# VCAMixer.net
KiCad netlist of a schematic drawn in EAGLE
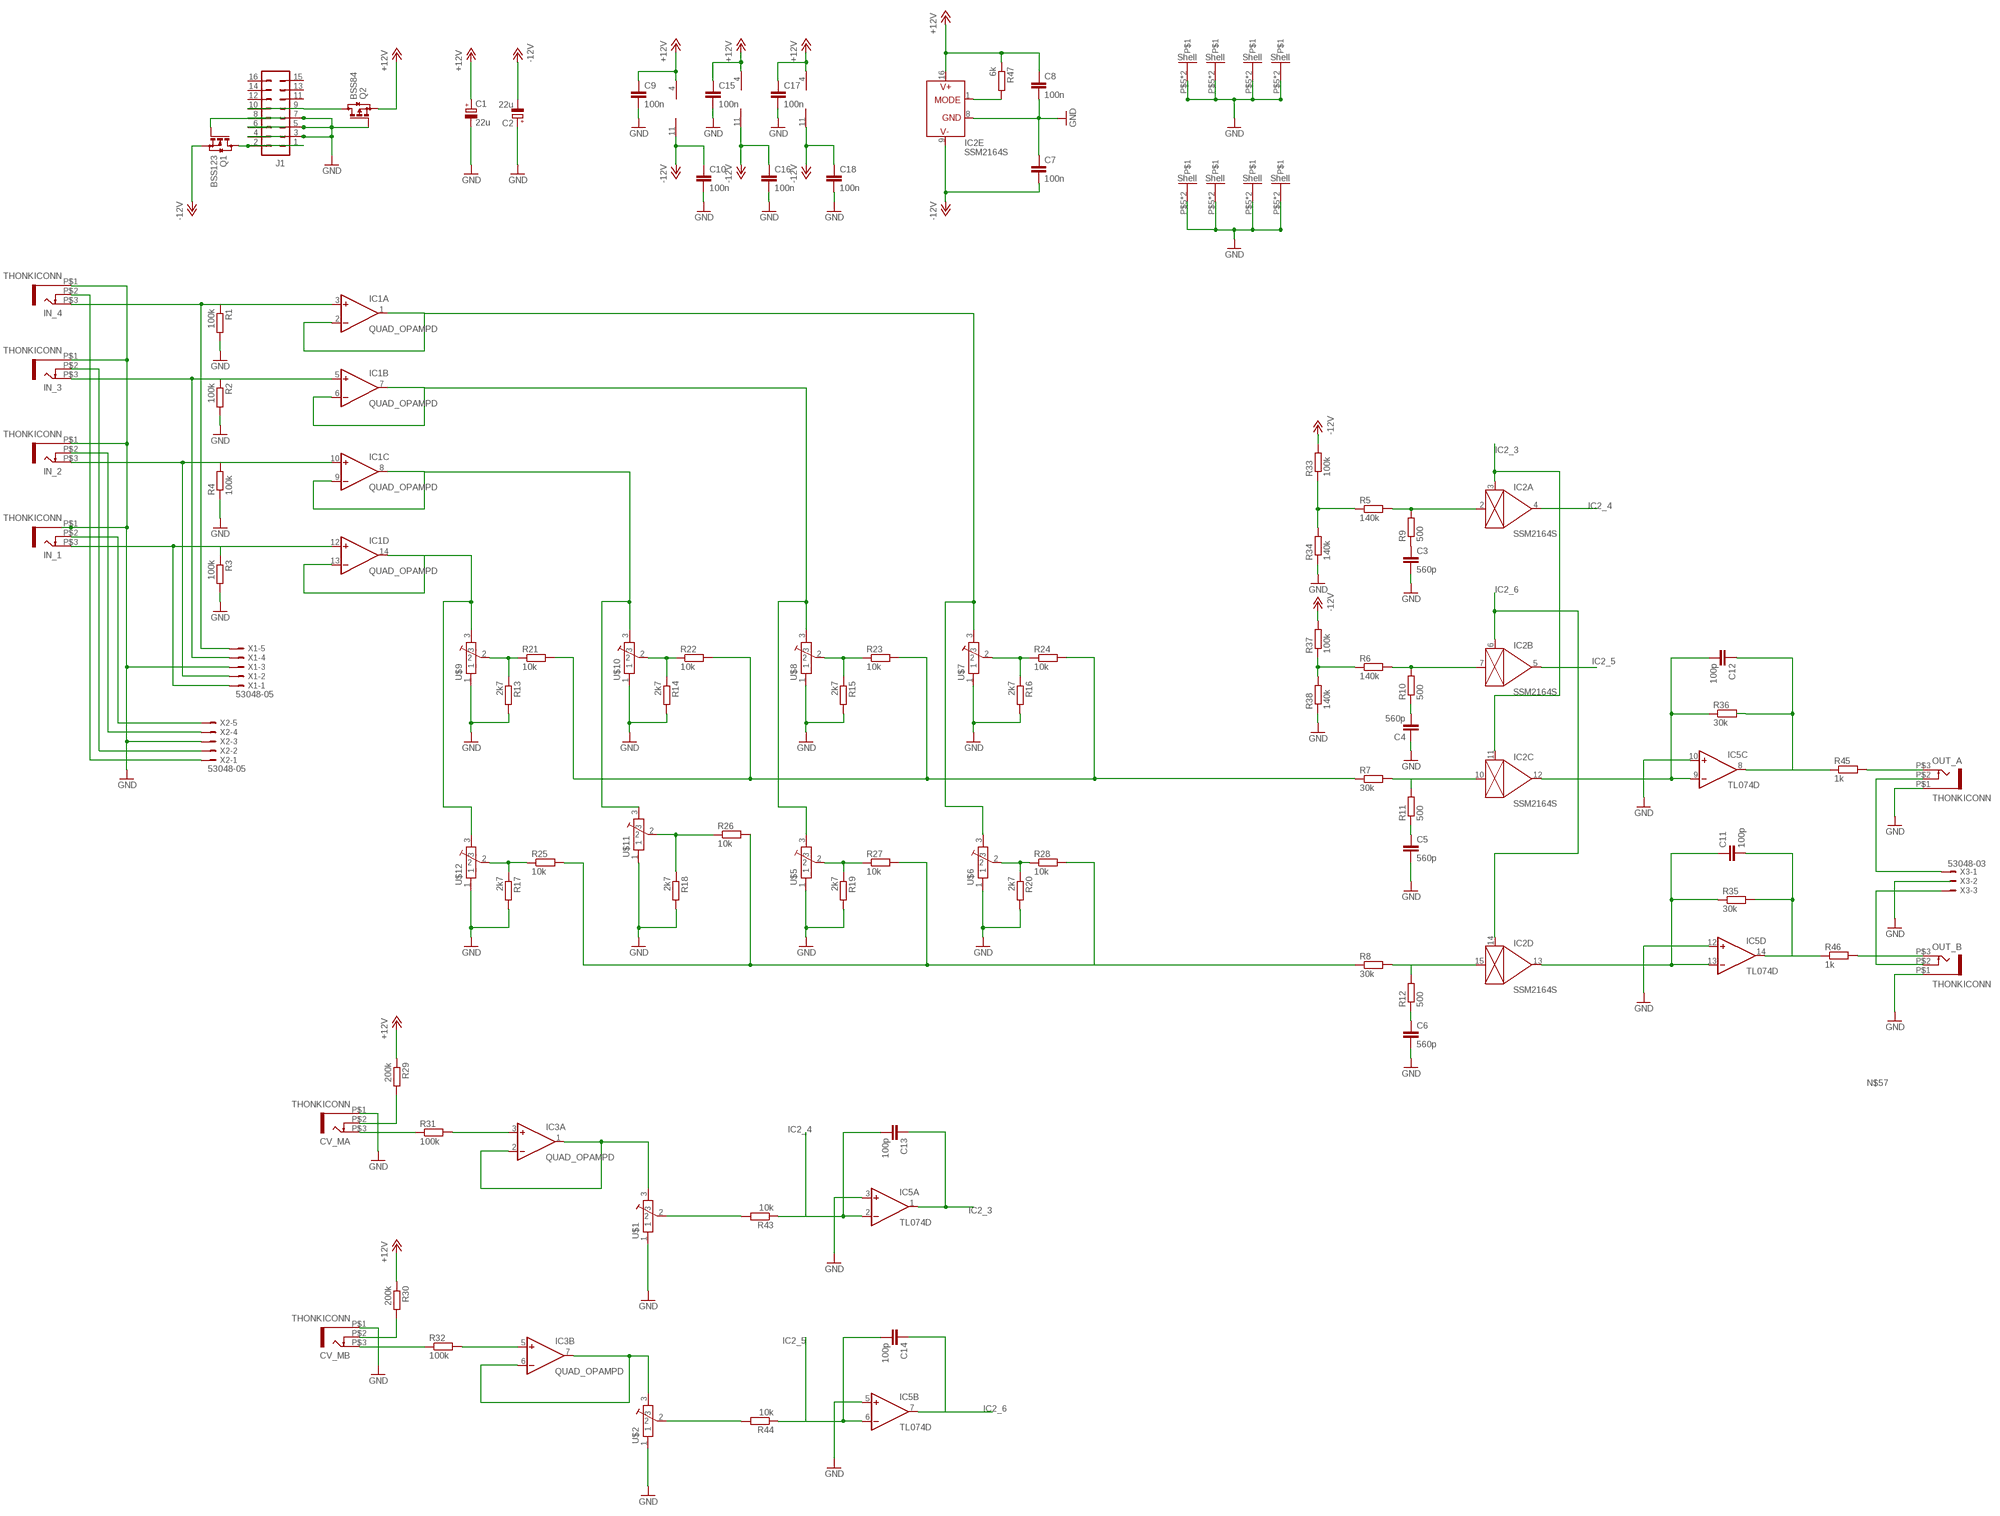
[diagram p0: schematic, sheet 1]

(export (version "E")
  (design (tool "Eeschema 10.0.6"))
  (components
    (comp (ref "C1")
      (value "22u")
      (footprint "eagle-import:153CLV-0505")
      (libsource (lib "eagle-import") (part "CPOL-EU153CLV-0505"))
    )
    (comp (ref "C2")
      (value "22u")
      (footprint "eagle-import:153CLV-0505")
      (libsource (lib "eagle-import") (part "CPOL-EU153CLV-0505"))
    )
    (comp (ref "C3")
      (value "560p")
      (footprint "eagle-import:C0603K")
      (libsource (lib "eagle-import") (part "C-EUC0603K"))
    )
    (comp (ref "C4")
      (value "560p")
      (footprint "eagle-import:C0603K")
      (libsource (lib "eagle-import") (part "C-EUC0603K"))
    )
    (comp (ref "C5")
      (value "560p")
      (footprint "eagle-import:C0603K")
      (libsource (lib "eagle-import") (part "C-EUC0603K"))
    )
    (comp (ref "C6")
      (value "560p")
      (footprint "eagle-import:C0603K")
      (libsource (lib "eagle-import") (part "C-EUC0603K"))
    )
    (comp (ref "C7")
      (value "100n")
      (footprint "eagle-import:C0603K")
      (libsource (lib "eagle-import") (part "C-EUC0603K"))
    )
    (comp (ref "C8")
      (value "100n")
      (footprint "eagle-import:C0603K")
      (libsource (lib "eagle-import") (part "C-EUC0603K"))
    )
    (comp (ref "C9")
      (value "100n")
      (footprint "eagle-import:C0603K")
      (libsource (lib "eagle-import") (part "C-EUC0603K"))
    )
    (comp (ref "C10")
      (value "100n")
      (footprint "eagle-import:C0603K")
      (libsource (lib "eagle-import") (part "C-EUC0603K"))
    )
    (comp (ref "C11")
      (value "100p")
      (footprint "eagle-import:C0603K")
      (libsource (lib "eagle-import") (part "C-EUC0603K"))
    )
    (comp (ref "C12")
      (value "100p")
      (footprint "eagle-import:C0603K")
      (libsource (lib "eagle-import") (part "C-EUC0603K"))
    )
    (comp (ref "C13")
      (value "100p")
      (footprint "eagle-import:C0603K")
      (libsource (lib "eagle-import") (part "C-EUC0603K"))
    )
    (comp (ref "C14")
      (value "100p")
      (footprint "eagle-import:C0603K")
      (libsource (lib "eagle-import") (part "C-EUC0603K"))
    )
    (comp (ref "C15")
      (value "100n")
      (footprint "eagle-import:C0603K")
      (libsource (lib "eagle-import") (part "C-EUC0603K"))
    )
    (comp (ref "C16")
      (value "100n")
      (footprint "eagle-import:C0603K")
      (libsource (lib "eagle-import") (part "C-EUC0603K"))
    )
    (comp (ref "C17")
      (value "100n")
      (footprint "eagle-import:C0603K")
      (libsource (lib "eagle-import") (part "C-EUC0603K"))
    )
    (comp (ref "C18")
      (value "100n")
      (footprint "eagle-import:C0603K")
      (libsource (lib "eagle-import") (part "C-EUC0603K"))
    )
    (comp (ref "CV_MA")
      (value "THONKICONN")
      (footprint "eagle-import:THONKICONN")
      (libsource (lib "eagle-import") (part "THONKICONN"))
    )
    (comp (ref "CV_MB")
      (value "THONKICONN")
      (footprint "eagle-import:THONKICONN")
      (libsource (lib "eagle-import") (part "THONKICONN"))
    )
    (comp (ref "IC1")
      (value "QUAD_OPAMPD")
      (footprint "eagle-import:SO14")
      (libsource (lib "eagle-import") (part "QUAD_OPAMPD"))
    )
    (comp (ref "IC2")
      (value "SSM2164S")
      (footprint "eagle-import:SOIC16N")
      (libsource (lib "eagle-import") (part "SSM2164S"))
    )
    (comp (ref "IC3")
      (value "QUAD_OPAMPD")
      (footprint "eagle-import:SO14")
      (libsource (lib "eagle-import") (part "QUAD_OPAMPD"))
    )
    (comp (ref "IC5")
      (value "TL074D")
      (footprint "eagle-import:SO14")
      (libsource (lib "eagle-import") (part "TL074D"))
    )
    (comp (ref "IN_1")
      (value "THONKICONN")
      (footprint "eagle-import:THONKICONN")
      (libsource (lib "eagle-import") (part "THONKICONN"))
    )
    (comp (ref "IN_2")
      (value "THONKICONN")
      (footprint "eagle-import:THONKICONN")
      (libsource (lib "eagle-import") (part "THONKICONN"))
    )
    (comp (ref "IN_3")
      (value "THONKICONN")
      (footprint "eagle-import:THONKICONN")
      (libsource (lib "eagle-import") (part "THONKICONN"))
    )
    (comp (ref "IN_4")
      (value "THONKICONN")
      (footprint "eagle-import:THONKICONN")
      (libsource (lib "eagle-import") (part "THONKICONN"))
    )
    (comp (ref "J1")
      (value "M08X2")
      (footprint "eagle-import:2X8")
      (libsource (lib "eagle-import") (part "M08X2"))
    )
    (comp (ref "OUT_A")
      (value "THONKICONN")
      (footprint "eagle-import:THONKICONN")
      (libsource (lib "eagle-import") (part "THONKICONN"))
    )
    (comp (ref "OUT_B")
      (value "THONKICONN")
      (footprint "eagle-import:THONKICONN")
      (libsource (lib "eagle-import") (part "THONKICONN"))
    )
    (comp (ref "Q1")
      (value "BSS123")
      (footprint "eagle-import:SOT23")
      (libsource (lib "eagle-import") (part "BSS123"))
    )
    (comp (ref "Q2")
      (value "BSS84")
      (footprint "eagle-import:SOT23")
      (libsource (lib "eagle-import") (part "BSS84"))
    )
    (comp (ref "R1")
      (value "100k")
      (footprint "eagle-import:0603")
      (libsource (lib "eagle-import") (part "R-EU_0603"))
    )
    (comp (ref "R2")
      (value "100k")
      (footprint "eagle-import:0603")
      (libsource (lib "eagle-import") (part "R-EU_0603"))
    )
    (comp (ref "R3")
      (value "100k")
      (footprint "eagle-import:0603")
      (libsource (lib "eagle-import") (part "R-EU_0603"))
    )
    (comp (ref "R4")
      (value "100k")
      (footprint "eagle-import:0603")
      (libsource (lib "eagle-import") (part "R-EU_0603"))
    )
    (comp (ref "R5")
      (value "140k")
      (footprint "eagle-import:0603")
      (libsource (lib "eagle-import") (part "R-EU_0603"))
    )
    (comp (ref "R6")
      (value "140k")
      (footprint "eagle-import:0603")
      (libsource (lib "eagle-import") (part "R-EU_0603"))
    )
    (comp (ref "R7")
      (value "30k")
      (footprint "eagle-import:0603")
      (libsource (lib "eagle-import") (part "R-EU_0603"))
    )
    (comp (ref "R8")
      (value "30k")
      (footprint "eagle-import:0603")
      (libsource (lib "eagle-import") (part "R-EU_0603"))
    )
    (comp (ref "R9")
      (value "500")
      (footprint "eagle-import:0603")
      (libsource (lib "eagle-import") (part "R-EU_0603"))
    )
    (comp (ref "R10")
      (value "500")
      (footprint "eagle-import:0603")
      (libsource (lib "eagle-import") (part "R-EU_0603"))
    )
    (comp (ref "R11")
      (value "500")
      (footprint "eagle-import:0603")
      (libsource (lib "eagle-import") (part "R-EU_0603"))
    )
    (comp (ref "R12")
      (value "500")
      (footprint "eagle-import:0603")
      (libsource (lib "eagle-import") (part "R-EU_0603"))
    )
    (comp (ref "R13")
      (value "2k7")
      (footprint "eagle-import:0603")
      (libsource (lib "eagle-import") (part "R-EU_0603"))
    )
    (comp (ref "R14")
      (value "2k7")
      (footprint "eagle-import:0603")
      (libsource (lib "eagle-import") (part "R-EU_0603"))
    )
    (comp (ref "R15")
      (value "2k7")
      (footprint "eagle-import:0603")
      (libsource (lib "eagle-import") (part "R-EU_0603"))
    )
    (comp (ref "R16")
      (value "2k7")
      (footprint "eagle-import:0603")
      (libsource (lib "eagle-import") (part "R-EU_0603"))
    )
    (comp (ref "R17")
      (value "2k7")
      (footprint "eagle-import:0603")
      (libsource (lib "eagle-import") (part "R-EU_0603"))
    )
    (comp (ref "R18")
      (value "2k7")
      (footprint "eagle-import:0603")
      (libsource (lib "eagle-import") (part "R-EU_0603"))
    )
    (comp (ref "R19")
      (value "2k7")
      (footprint "eagle-import:0603")
      (libsource (lib "eagle-import") (part "R-EU_0603"))
    )
    (comp (ref "R20")
      (value "2k7")
      (footprint "eagle-import:0603")
      (libsource (lib "eagle-import") (part "R-EU_0603"))
    )
    (comp (ref "R21")
      (value "10k")
      (footprint "eagle-import:0603")
      (libsource (lib "eagle-import") (part "R-EU_0603"))
    )
    (comp (ref "R22")
      (value "10k")
      (footprint "eagle-import:0603")
      (libsource (lib "eagle-import") (part "R-EU_0603"))
    )
    (comp (ref "R23")
      (value "10k")
      (footprint "eagle-import:0603")
      (libsource (lib "eagle-import") (part "R-EU_0603"))
    )
    (comp (ref "R24")
      (value "10k")
      (footprint "eagle-import:0603")
      (libsource (lib "eagle-import") (part "R-EU_0603"))
    )
    (comp (ref "R25")
      (value "10k")
      (footprint "eagle-import:0603")
      (libsource (lib "eagle-import") (part "R-EU_0603"))
    )
    (comp (ref "R26")
      (value "10k")
      (footprint "eagle-import:0603")
      (libsource (lib "eagle-import") (part "R-EU_0603"))
    )
    (comp (ref "R27")
      (value "10k")
      (footprint "eagle-import:0603")
      (libsource (lib "eagle-import") (part "R-EU_0603"))
    )
    (comp (ref "R28")
      (value "10k")
      (footprint "eagle-import:0603")
      (libsource (lib "eagle-import") (part "R-EU_0603"))
    )
    (comp (ref "R29")
      (value "200k")
      (footprint "eagle-import:0603")
      (libsource (lib "eagle-import") (part "R-EU_0603"))
    )
    (comp (ref "R30")
      (value "200k")
      (footprint "eagle-import:0603")
      (libsource (lib "eagle-import") (part "R-EU_0603"))
    )
    (comp (ref "R31")
      (value "100k")
      (footprint "eagle-import:0603")
      (libsource (lib "eagle-import") (part "R-EU_0603"))
    )
    (comp (ref "R32")
      (value "100k")
      (footprint "eagle-import:0603")
      (libsource (lib "eagle-import") (part "R-EU_0603"))
    )
    (comp (ref "R33")
      (value "100k")
      (footprint "eagle-import:0603")
      (libsource (lib "eagle-import") (part "R-EU_0603"))
    )
    (comp (ref "R34")
      (value "140k")
      (footprint "eagle-import:0603")
      (libsource (lib "eagle-import") (part "R-EU_0603"))
    )
    (comp (ref "R35")
      (value "30k")
      (footprint "eagle-import:0603")
      (libsource (lib "eagle-import") (part "R-EU_0603"))
    )
    (comp (ref "R36")
      (value "30k")
      (footprint "eagle-import:0603")
      (libsource (lib "eagle-import") (part "R-EU_0603"))
    )
    (comp (ref "R37")
      (value "100k")
      (footprint "eagle-import:0603")
      (libsource (lib "eagle-import") (part "R-EU_0603"))
    )
    (comp (ref "R38")
      (value "140k")
      (footprint "eagle-import:0603")
      (libsource (lib "eagle-import") (part "R-EU_0603"))
    )
    (comp (ref "R43")
      (value "10k")
      (footprint "eagle-import:0603")
      (libsource (lib "eagle-import") (part "R-EU_0603"))
    )
    (comp (ref "R44")
      (value "10k")
      (footprint "eagle-import:0603")
      (libsource (lib "eagle-import") (part "R-EU_0603"))
    )
    (comp (ref "R45")
      (value "1k")
      (footprint "eagle-import:0603")
      (libsource (lib "eagle-import") (part "R-EU_0603"))
    )
    (comp (ref "R46")
      (value "1k")
      (footprint "eagle-import:0603")
      (libsource (lib "eagle-import") (part "R-EU_0603"))
    )
    (comp (ref "R47")
      (value "6k")
      (footprint "eagle-import:0603")
      (libsource (lib "eagle-import") (part "R-EU_0603"))
    )
    (comp (ref "U$1")
      (value "POT-ALPS-RK09L1140")
      (footprint "eagle-import:POT-ALPS-RK09L1140")
      (libsource (lib "eagle-import") (part "POT-ALPS-RK09L1140"))
    )
    (comp (ref "U$2")
      (value "POT-ALPS-RK09L1140")
      (footprint "eagle-import:POT-ALPS-RK09L1140")
      (libsource (lib "eagle-import") (part "POT-ALPS-RK09L1140"))
    )
    (comp (ref "U$5")
      (value "POT-ALPS-RK09L1140")
      (footprint "eagle-import:POT-ALPS-RK09L1140")
      (libsource (lib "eagle-import") (part "POT-ALPS-RK09L1140"))
    )
    (comp (ref "U$6")
      (value "POT-ALPS-RK09L1140")
      (footprint "eagle-import:POT-ALPS-RK09L1140")
      (libsource (lib "eagle-import") (part "POT-ALPS-RK09L1140"))
    )
    (comp (ref "U$7")
      (value "POT-ALPS-RK09L1140")
      (footprint "eagle-import:POT-ALPS-RK09L1140")
      (libsource (lib "eagle-import") (part "POT-ALPS-RK09L1140"))
    )
    (comp (ref "U$8")
      (value "POT-ALPS-RK09L1140")
      (footprint "eagle-import:POT-ALPS-RK09L1140")
      (libsource (lib "eagle-import") (part "POT-ALPS-RK09L1140"))
    )
    (comp (ref "U$9")
      (value "POT-ALPS-RK09L1140")
      (footprint "eagle-import:POT-ALPS-RK09L1140")
      (libsource (lib "eagle-import") (part "POT-ALPS-RK09L1140"))
    )
    (comp (ref "U$10")
      (value "POT-ALPS-RK09L1140")
      (footprint "eagle-import:POT-ALPS-RK09L1140")
      (libsource (lib "eagle-import") (part "POT-ALPS-RK09L1140"))
    )
    (comp (ref "U$11")
      (value "POT-ALPS-RK09L1140")
      (footprint "eagle-import:POT-ALPS-RK09L1140")
      (libsource (lib "eagle-import") (part "POT-ALPS-RK09L1140"))
    )
    (comp (ref "U$12")
      (value "POT-ALPS-RK09L1140")
      (footprint "eagle-import:POT-ALPS-RK09L1140")
      (libsource (lib "eagle-import") (part "POT-ALPS-RK09L1140"))
    )
    (comp (ref "X1")
      (value "53048-05")
      (footprint "eagle-import:53048-05")
      (fields (field (name "MF") "MOLEX") (field (name "MPN") "53048-0510"))
      (libsource (lib "eagle-import") (part "53?-05048"))
    )
    (comp (ref "X2")
      (value "53048-05")
      (footprint "eagle-import:53048-05")
      (fields (field (name "MF") "MOLEX") (field (name "MPN") "53048-0510"))
      (libsource (lib "eagle-import") (part "53?-05048"))
    )
    (comp (ref "X3")
      (value "53048-03")
      (footprint "eagle-import:53048-03")
      (fields (field (name "MF") "WALDOM/MOLEX") (field (name "MPN") "53048-0310"))
      (libsource (lib "eagle-import") (part "53?-03048"))
    )
  )
  (nets
    (net (code "1") (name "+12V") (class "Default")
      (node (ref "C1") (pin "+") (pinfunction "+_+") (pintype "passive"))
      (node (ref "C15") (pin "1") (pinfunction "1_1") (pintype "passive"))
      (node (ref "C17") (pin "1") (pinfunction "1_1") (pintype "passive"))
      (node (ref "C8") (pin "1") (pinfunction "1_1") (pintype "passive"))
      (node (ref "C9") (pin "1") (pinfunction "1_1") (pintype "passive"))
      (node (ref "IC1") (pin "4") (pinfunction "V+_4") (pintype "power_in"))
      (node (ref "IC2") (pin "16") (pinfunction "V+_16") (pintype "power_in"))
      (node (ref "IC3") (pin "4") (pinfunction "V+_4") (pintype "power_in"))
      (node (ref "IC5") (pin "4") (pinfunction "V+_4") (pintype "power_in"))
      (node (ref "Q2") (pin "2") (pinfunction "S_2") (pintype "passive"))
      (node (ref "R29") (pin "1") (pinfunction "1_1") (pintype "passive"))
      (node (ref "R30") (pin "1") (pinfunction "1_1") (pintype "passive"))
      (node (ref "R47") (pin "1") (pinfunction "1_1") (pintype "passive"))
    )
    (net (code "2") (name "-12V") (class "Default")
      (node (ref "C10") (pin "1") (pinfunction "1_1") (pintype "passive"))
      (node (ref "C16") (pin "1") (pinfunction "1_1") (pintype "passive"))
      (node (ref "C18") (pin "1") (pinfunction "1_1") (pintype "passive"))
      (node (ref "C2") (pin "-") (pinfunction "-_-") (pintype "passive"))
      (node (ref "C7") (pin "2") (pinfunction "2_2") (pintype "passive"))
      (node (ref "IC1") (pin "11") (pinfunction "V-_11") (pintype "power_in"))
      (node (ref "IC2") (pin "9") (pinfunction "V-_9") (pintype "power_in"))
      (node (ref "IC3") (pin "11") (pinfunction "V-_11") (pintype "power_in"))
      (node (ref "IC5") (pin "11") (pinfunction "V-_11") (pintype "power_in"))
      (node (ref "Q1") (pin "2") (pinfunction "S_2") (pintype "passive"))
      (node (ref "R33") (pin "2") (pinfunction "2_2") (pintype "passive"))
      (node (ref "R37") (pin "2") (pinfunction "2_2") (pintype "passive"))
    )
    (net (code "3") (name "/IC2_3") (class "Default")
      (node (ref "C13") (pin "1") (pinfunction "1_1") (pintype "passive"))
      (node (ref "IC2") (pin "11") (pinfunction "CTRL_11") (pintype "input"))
      (node (ref "IC2") (pin "3") (pinfunction "CTRL_3") (pintype "input"))
      (node (ref "IC5") (pin "1") (pinfunction "OUT_1") (pintype "output"))
    )
    (net (code "4") (name "/IC2_4") (class "Default")
      (node (ref "C13") (pin "2") (pinfunction "2_2") (pintype "passive"))
      (node (ref "IC2") (pin "4") (pinfunction "OUT_4") (pintype "output"))
      (node (ref "IC5") (pin "2") (pinfunction "-IN_2") (pintype "input"))
      (node (ref "R43") (pin "1") (pinfunction "1_1") (pintype "passive"))
    )
    (net (code "5") (name "/IC2_5") (class "Default")
      (node (ref "C14") (pin "2") (pinfunction "2_2") (pintype "passive"))
      (node (ref "IC2") (pin "5") (pinfunction "OUT_5") (pintype "output"))
      (node (ref "IC5") (pin "6") (pinfunction "-IN_6") (pintype "input"))
      (node (ref "R44") (pin "1") (pinfunction "1_1") (pintype "passive"))
    )
    (net (code "6") (name "/IC2_6") (class "Default")
      (node (ref "C14") (pin "1") (pinfunction "1_1") (pintype "passive"))
      (node (ref "IC2") (pin "14") (pinfunction "CTRL_14") (pintype "input"))
      (node (ref "IC2") (pin "6") (pinfunction "CTRL_6") (pintype "input"))
      (node (ref "IC5") (pin "7") (pinfunction "OUT_7") (pintype "output"))
    )
    (net (code "7") (name "/N$57") (class "Default")
      (node (ref "OUT_B") (pin "P$2") (pinfunction "4_P$2") (pintype "passive"))
      (node (ref "X3") (pin "3") (pinfunction "S_3") (pintype "passive"))
    )
    (net (code "8") (name "GND") (class "Default")
      (node (ref "C1") (pin "-") (pinfunction "-_-") (pintype "passive"))
      (node (ref "C10") (pin "2") (pinfunction "2_2") (pintype "passive"))
      (node (ref "C15") (pin "2") (pinfunction "2_2") (pintype "passive"))
      (node (ref "C16") (pin "2") (pinfunction "2_2") (pintype "passive"))
      (node (ref "C17") (pin "2") (pinfunction "2_2") (pintype "passive"))
      (node (ref "C18") (pin "2") (pinfunction "2_2") (pintype "passive"))
      (node (ref "C2") (pin "+") (pinfunction "+_+") (pintype "passive"))
      (node (ref "C3") (pin "2") (pinfunction "2_2") (pintype "passive"))
      (node (ref "C4") (pin "1") (pinfunction "1_1") (pintype "passive"))
      (node (ref "C5") (pin "2") (pinfunction "2_2") (pintype "passive"))
      (node (ref "C6") (pin "2") (pinfunction "2_2") (pintype "passive"))
      (node (ref "C7") (pin "1") (pinfunction "1_1") (pintype "passive"))
      (node (ref "C8") (pin "2") (pinfunction "2_2") (pintype "passive"))
      (node (ref "C9") (pin "2") (pinfunction "2_2") (pintype "passive"))
      (node (ref "CV_MA") (pin "P$1") (pinfunction "5_P$1") (pintype "passive"))
      (node (ref "CV_MB") (pin "P$1") (pinfunction "5_P$1") (pintype "passive"))
      (node (ref "IC2") (pin "8") (pinfunction "GND_8") (pintype "power_in"))
      (node (ref "IC5") (pin "10") (pinfunction "+IN_10") (pintype "input"))
      (node (ref "IC5") (pin "12") (pinfunction "+IN_12") (pintype "input"))
      (node (ref "IC5") (pin "3") (pinfunction "+IN_3") (pintype "input"))
      (node (ref "IC5") (pin "5") (pinfunction "+IN_5") (pintype "input"))
      (node (ref "IN_1") (pin "P$1") (pinfunction "5_P$1") (pintype "passive"))
      (node (ref "IN_2") (pin "P$1") (pinfunction "5_P$1") (pintype "passive"))
      (node (ref "IN_3") (pin "P$1") (pinfunction "5_P$1") (pintype "passive"))
      (node (ref "IN_4") (pin "P$1") (pinfunction "5_P$1") (pintype "passive"))
      (node (ref "J1") (pin "3") (pinfunction "3_3") (pintype "passive"))
      (node (ref "J1") (pin "5") (pinfunction "5_5") (pintype "passive"))
      (node (ref "J1") (pin "7") (pinfunction "7_7") (pintype "passive"))
      (node (ref "OUT_A") (pin "P$1") (pinfunction "5_P$1") (pintype "passive"))
      (node (ref "OUT_B") (pin "P$1") (pinfunction "5_P$1") (pintype "passive"))
      (node (ref "Q2") (pin "1") (pinfunction "G_1") (pintype "passive"))
      (node (ref "R1") (pin "2") (pinfunction "2_2") (pintype "passive"))
      (node (ref "R13") (pin "2") (pinfunction "2_2") (pintype "passive"))
      (node (ref "R14") (pin "2") (pinfunction "2_2") (pintype "passive"))
      (node (ref "R15") (pin "2") (pinfunction "2_2") (pintype "passive"))
      (node (ref "R16") (pin "2") (pinfunction "2_2") (pintype "passive"))
      (node (ref "R17") (pin "2") (pinfunction "2_2") (pintype "passive"))
      (node (ref "R18") (pin "2") (pinfunction "2_2") (pintype "passive"))
      (node (ref "R19") (pin "2") (pinfunction "2_2") (pintype "passive"))
      (node (ref "R2") (pin "2") (pinfunction "2_2") (pintype "passive"))
      (node (ref "R20") (pin "2") (pinfunction "2_2") (pintype "passive"))
      (node (ref "R3") (pin "2") (pinfunction "2_2") (pintype "passive"))
      (node (ref "R34") (pin "1") (pinfunction "1_1") (pintype "passive"))
      (node (ref "R38") (pin "1") (pinfunction "1_1") (pintype "passive"))
      (node (ref "R4") (pin "1") (pinfunction "1_1") (pintype "passive"))
      (node (ref "U$1") (pin "1") (pinfunction "1_1") (pintype "bidirectional"))
      (node (ref "U$10") (pin "1") (pinfunction "1_1") (pintype "bidirectional"))
      (node (ref "U$10") (pin "P$5") (pinfunction "P$1_P$5") (pintype "bidirectional"))
      (node (ref "U$10") (pin "P$6") (pinfunction "P$1_P$6") (pintype "bidirectional"))
      (node (ref "U$11") (pin "1") (pinfunction "1_1") (pintype "bidirectional"))
      (node (ref "U$11") (pin "P$5") (pinfunction "P$1_P$5") (pintype "bidirectional"))
      (node (ref "U$11") (pin "P$6") (pinfunction "P$1_P$6") (pintype "bidirectional"))
      (node (ref "U$12") (pin "1") (pinfunction "1_1") (pintype "bidirectional"))
      (node (ref "U$12") (pin "P$5") (pinfunction "P$1_P$5") (pintype "bidirectional"))
      (node (ref "U$12") (pin "P$6") (pinfunction "P$1_P$6") (pintype "bidirectional"))
      (node (ref "U$2") (pin "1") (pinfunction "1_1") (pintype "bidirectional"))
      (node (ref "U$5") (pin "1") (pinfunction "1_1") (pintype "bidirectional"))
      (node (ref "U$5") (pin "P$5") (pinfunction "P$1_P$5") (pintype "bidirectional"))
      (node (ref "U$5") (pin "P$6") (pinfunction "P$1_P$6") (pintype "bidirectional"))
      (node (ref "U$6") (pin "1") (pinfunction "1_1") (pintype "bidirectional"))
      (node (ref "U$6") (pin "P$5") (pinfunction "P$1_P$5") (pintype "bidirectional"))
      (node (ref "U$6") (pin "P$6") (pinfunction "P$1_P$6") (pintype "bidirectional"))
      (node (ref "U$7") (pin "1") (pinfunction "1_1") (pintype "bidirectional"))
      (node (ref "U$7") (pin "P$5") (pinfunction "P$1_P$5") (pintype "bidirectional"))
      (node (ref "U$7") (pin "P$6") (pinfunction "P$1_P$6") (pintype "bidirectional"))
      (node (ref "U$8") (pin "1") (pinfunction "1_1") (pintype "bidirectional"))
      (node (ref "U$8") (pin "P$5") (pinfunction "P$1_P$5") (pintype "bidirectional"))
      (node (ref "U$8") (pin "P$6") (pinfunction "P$1_P$6") (pintype "bidirectional"))
      (node (ref "U$9") (pin "1") (pinfunction "1_1") (pintype "bidirectional"))
      (node (ref "U$9") (pin "P$5") (pinfunction "P$1_P$5") (pintype "bidirectional"))
      (node (ref "U$9") (pin "P$6") (pinfunction "P$1_P$6") (pintype "bidirectional"))
      (node (ref "X1") (pin "3") (pinfunction "S_3") (pintype "passive"))
      (node (ref "X2") (pin "3") (pinfunction "S_3") (pintype "passive"))
    )
    (net (code "9") (name "Net-(C3-Pad1)") (class "Default")
      (node (ref "C3") (pin "1") (pinfunction "1_1") (pintype "passive"))
      (node (ref "R9") (pin "1") (pinfunction "1_1") (pintype "passive"))
    )
    (net (code "10") (name "Net-(C4-Pad2)") (class "Default")
      (node (ref "C4") (pin "2") (pinfunction "2_2") (pintype "passive"))
      (node (ref "R10") (pin "1") (pinfunction "1_1") (pintype "passive"))
    )
    (net (code "11") (name "Net-(C5-Pad1)") (class "Default")
      (node (ref "C5") (pin "1") (pinfunction "1_1") (pintype "passive"))
      (node (ref "R11") (pin "1") (pinfunction "1_1") (pintype "passive"))
    )
    (net (code "12") (name "Net-(C6-Pad1)") (class "Default")
      (node (ref "C6") (pin "1") (pinfunction "1_1") (pintype "passive"))
      (node (ref "R12") (pin "1") (pinfunction "1_1") (pintype "passive"))
    )
    (net (code "13") (name "Net-(CV_MA-3)") (class "Default")
      (node (ref "CV_MA") (pin "P$3") (pinfunction "3_P$3") (pintype "passive"))
      (node (ref "R31") (pin "1") (pinfunction "1_1") (pintype "passive"))
    )
    (net (code "14") (name "Net-(CV_MA-4)") (class "Default")
      (node (ref "CV_MA") (pin "P$2") (pinfunction "4_P$2") (pintype "passive"))
      (node (ref "R29") (pin "2") (pinfunction "2_2") (pintype "passive"))
    )
    (net (code "15") (name "Net-(CV_MB-3)") (class "Default")
      (node (ref "CV_MB") (pin "P$3") (pinfunction "3_P$3") (pintype "passive"))
      (node (ref "R32") (pin "1") (pinfunction "1_1") (pintype "passive"))
    )
    (net (code "16") (name "Net-(CV_MB-4)") (class "Default")
      (node (ref "CV_MB") (pin "P$2") (pinfunction "4_P$2") (pintype "passive"))
      (node (ref "R30") (pin "2") (pinfunction "2_2") (pintype "passive"))
    )
    (net (code "17") (name "Net-(IC1A-+IN)") (class "Default")
      (node (ref "IC1") (pin "3") (pinfunction "+IN_3") (pintype "input"))
      (node (ref "IN_4") (pin "P$3") (pinfunction "3_P$3") (pintype "passive"))
      (node (ref "R1") (pin "1") (pinfunction "1_1") (pintype "passive"))
      (node (ref "X1") (pin "5") (pinfunction "S_5") (pintype "passive"))
    )
    (net (code "18") (name "Net-(IC1A--IN)") (class "Default")
      (node (ref "IC1") (pin "1") (pinfunction "OUT_1") (pintype "output"))
      (node (ref "IC1") (pin "2") (pinfunction "-IN_2") (pintype "input"))
      (node (ref "U$6") (pin "3") (pinfunction "3_3") (pintype "bidirectional"))
      (node (ref "U$7") (pin "3") (pinfunction "3_3") (pintype "bidirectional"))
    )
    (net (code "19") (name "Net-(IC1B-+IN)") (class "Default")
      (node (ref "IC1") (pin "5") (pinfunction "+IN_5") (pintype "input"))
      (node (ref "IN_3") (pin "P$3") (pinfunction "3_P$3") (pintype "passive"))
      (node (ref "R2") (pin "1") (pinfunction "1_1") (pintype "passive"))
      (node (ref "X1") (pin "4") (pinfunction "S_4") (pintype "passive"))
    )
    (net (code "20") (name "Net-(IC1B--IN)") (class "Default")
      (node (ref "IC1") (pin "6") (pinfunction "-IN_6") (pintype "input"))
      (node (ref "IC1") (pin "7") (pinfunction "OUT_7") (pintype "output"))
      (node (ref "U$5") (pin "3") (pinfunction "3_3") (pintype "bidirectional"))
      (node (ref "U$8") (pin "3") (pinfunction "3_3") (pintype "bidirectional"))
    )
    (net (code "21") (name "Net-(IC1C-+IN)") (class "Default")
      (node (ref "IC1") (pin "10") (pinfunction "+IN_10") (pintype "input"))
      (node (ref "IN_2") (pin "P$3") (pinfunction "3_P$3") (pintype "passive"))
      (node (ref "R4") (pin "2") (pinfunction "2_2") (pintype "passive"))
      (node (ref "X1") (pin "2") (pinfunction "S_2") (pintype "passive"))
    )
    (net (code "22") (name "Net-(IC1C--IN)") (class "Default")
      (node (ref "IC1") (pin "8") (pinfunction "OUT_8") (pintype "output"))
      (node (ref "IC1") (pin "9") (pinfunction "-IN_9") (pintype "input"))
      (node (ref "U$10") (pin "3") (pinfunction "3_3") (pintype "bidirectional"))
      (node (ref "U$11") (pin "3") (pinfunction "3_3") (pintype "bidirectional"))
    )
    (net (code "23") (name "Net-(IC1D-+IN)") (class "Default")
      (node (ref "IC1") (pin "12") (pinfunction "+IN_12") (pintype "input"))
      (node (ref "IN_1") (pin "P$3") (pinfunction "3_P$3") (pintype "passive"))
      (node (ref "R3") (pin "1") (pinfunction "1_1") (pintype "passive"))
      (node (ref "X1") (pin "1") (pinfunction "S_1") (pintype "passive"))
    )
    (net (code "24") (name "Net-(IC1D--IN)") (class "Default")
      (node (ref "IC1") (pin "13") (pinfunction "-IN_13") (pintype "input"))
      (node (ref "IC1") (pin "14") (pinfunction "OUT_14") (pintype "output"))
      (node (ref "U$12") (pin "3") (pinfunction "3_3") (pintype "bidirectional"))
      (node (ref "U$9") (pin "3") (pinfunction "3_3") (pintype "bidirectional"))
    )
    (net (code "25") (name "Net-(IC2A-IN)") (class "Default")
      (node (ref "IC2") (pin "2") (pinfunction "IN_2") (pintype "input"))
      (node (ref "R5") (pin "2") (pinfunction "2_2") (pintype "passive"))
      (node (ref "R9") (pin "2") (pinfunction "2_2") (pintype "passive"))
    )
    (net (code "26") (name "Net-(IC2B-IN)") (class "Default")
      (node (ref "IC2") (pin "7") (pinfunction "IN_7") (pintype "input"))
      (node (ref "R10") (pin "2") (pinfunction "2_2") (pintype "passive"))
      (node (ref "R6") (pin "2") (pinfunction "2_2") (pintype "passive"))
    )
    (net (code "27") (name "Net-(IC2C-IN)") (class "Default")
      (node (ref "IC2") (pin "10") (pinfunction "IN_10") (pintype "input"))
      (node (ref "R11") (pin "2") (pinfunction "2_2") (pintype "passive"))
      (node (ref "R7") (pin "2") (pinfunction "2_2") (pintype "passive"))
    )
    (net (code "28") (name "Net-(IC2C-OUT)") (class "Default")
      (node (ref "C12") (pin "2") (pinfunction "2_2") (pintype "passive"))
      (node (ref "IC2") (pin "12") (pinfunction "OUT_12") (pintype "output"))
      (node (ref "IC5") (pin "9") (pinfunction "-IN_9") (pintype "input"))
      (node (ref "R36") (pin "1") (pinfunction "1_1") (pintype "passive"))
    )
    (net (code "29") (name "Net-(IC2D-IN)") (class "Default")
      (node (ref "IC2") (pin "15") (pinfunction "IN_15") (pintype "input"))
      (node (ref "R12") (pin "2") (pinfunction "2_2") (pintype "passive"))
      (node (ref "R8") (pin "2") (pinfunction "2_2") (pintype "passive"))
    )
    (net (code "30") (name "Net-(IC2D-OUT)") (class "Default")
      (node (ref "C11") (pin "1") (pinfunction "1_1") (pintype "passive"))
      (node (ref "IC2") (pin "13") (pinfunction "OUT_13") (pintype "output"))
      (node (ref "IC5") (pin "13") (pinfunction "-IN_13") (pintype "input"))
      (node (ref "R35") (pin "1") (pinfunction "1_1") (pintype "passive"))
    )
    (net (code "31") (name "Net-(IC2E-MODE)") (class "Default")
      (node (ref "IC2") (pin "1") (pinfunction "MODE_1") (pintype "input"))
      (node (ref "R47") (pin "2") (pinfunction "2_2") (pintype "passive"))
    )
    (net (code "32") (name "Net-(IC3A-+IN)") (class "Default")
      (node (ref "IC3") (pin "3") (pinfunction "+IN_3") (pintype "input"))
      (node (ref "R31") (pin "2") (pinfunction "2_2") (pintype "passive"))
    )
    (net (code "33") (name "Net-(IC3A--IN)") (class "Default")
      (node (ref "IC3") (pin "1") (pinfunction "OUT_1") (pintype "output"))
      (node (ref "IC3") (pin "2") (pinfunction "-IN_2") (pintype "input"))
      (node (ref "U$1") (pin "3") (pinfunction "3_3") (pintype "bidirectional"))
    )
    (net (code "34") (name "Net-(IC3B-+IN)") (class "Default")
      (node (ref "IC3") (pin "5") (pinfunction "+IN_5") (pintype "input"))
      (node (ref "R32") (pin "2") (pinfunction "2_2") (pintype "passive"))
    )
    (net (code "35") (name "Net-(IC3B--IN)") (class "Default")
      (node (ref "IC3") (pin "6") (pinfunction "-IN_6") (pintype "input"))
      (node (ref "IC3") (pin "7") (pinfunction "OUT_7") (pintype "output"))
      (node (ref "U$2") (pin "3") (pinfunction "3_3") (pintype "bidirectional"))
    )
    (net (code "36") (name "Net-(IC5C-OUT)") (class "Default")
      (node (ref "C12") (pin "1") (pinfunction "1_1") (pintype "passive"))
      (node (ref "IC5") (pin "8") (pinfunction "OUT_8") (pintype "output"))
      (node (ref "R36") (pin "2") (pinfunction "2_2") (pintype "passive"))
      (node (ref "R45") (pin "1") (pinfunction "1_1") (pintype "passive"))
    )
    (net (code "37") (name "Net-(IC5D-OUT)") (class "Default")
      (node (ref "C11") (pin "2") (pinfunction "2_2") (pintype "passive"))
      (node (ref "IC5") (pin "14") (pinfunction "OUT_14") (pintype "output"))
      (node (ref "R35") (pin "2") (pinfunction "2_2") (pintype "passive"))
      (node (ref "R46") (pin "1") (pinfunction "1_1") (pintype "passive"))
    )
    (net (code "38") (name "Net-(IN_1-4)") (class "Default")
      (node (ref "IN_1") (pin "P$2") (pinfunction "4_P$2") (pintype "passive"))
      (node (ref "X2") (pin "5") (pinfunction "S_5") (pintype "passive"))
    )
    (net (code "39") (name "Net-(IN_2-4)") (class "Default")
      (node (ref "IN_2") (pin "P$2") (pinfunction "4_P$2") (pintype "passive"))
      (node (ref "X2") (pin "4") (pinfunction "S_4") (pintype "passive"))
    )
    (net (code "40") (name "Net-(IN_3-4)") (class "Default")
      (node (ref "IN_3") (pin "P$2") (pinfunction "4_P$2") (pintype "passive"))
      (node (ref "X2") (pin "2") (pinfunction "S_2") (pintype "passive"))
    )
    (net (code "41") (name "Net-(IN_4-4)") (class "Default")
      (node (ref "IN_4") (pin "P$2") (pinfunction "4_P$2") (pintype "passive"))
      (node (ref "X2") (pin "1") (pinfunction "S_1") (pintype "passive"))
    )
    (net (code "42") (name "Net-(OUT_A-3)") (class "Default")
      (node (ref "OUT_A") (pin "P$3") (pinfunction "3_P$3") (pintype "passive"))
      (node (ref "R45") (pin "2") (pinfunction "2_2") (pintype "passive"))
    )
    (net (code "43") (name "Net-(OUT_A-4)") (class "Default")
      (node (ref "OUT_A") (pin "P$2") (pinfunction "4_P$2") (pintype "passive"))
      (node (ref "X3") (pin "1") (pinfunction "S_1") (pintype "passive"))
    )
    (net (code "44") (name "Net-(OUT_B-3)") (class "Default")
      (node (ref "OUT_B") (pin "P$3") (pinfunction "3_P$3") (pintype "passive"))
      (node (ref "R46") (pin "2") (pinfunction "2_2") (pintype "passive"))
    )
    (net (code "45") (name "Net-(Q1-D)") (class "Default")
      (node (ref "J1") (pin "1") (pinfunction "1_1") (pintype "passive"))
      (node (ref "J1") (pin "2") (pinfunction "2_2") (pintype "passive"))
      (node (ref "Q1") (pin "3") (pinfunction "D_3") (pintype "passive"))
    )
    (net (code "46") (name "Net-(Q1-G)") (class "Default")
      (node (ref "J1") (pin "8") (pinfunction "8_8") (pintype "passive"))
      (node (ref "Q1") (pin "1") (pinfunction "G_1") (pintype "passive"))
    )
    (net (code "47") (name "Net-(Q2-D)") (class "Default")
      (node (ref "J1") (pin "10") (pinfunction "10_10") (pintype "passive"))
      (node (ref "J1") (pin "9") (pinfunction "9_9") (pintype "passive"))
      (node (ref "Q2") (pin "3") (pinfunction "D_3") (pintype "passive"))
    )
    (net (code "48") (name "Net-(R13-Pad1)") (class "Default")
      (node (ref "R13") (pin "1") (pinfunction "1_1") (pintype "passive"))
      (node (ref "R21") (pin "1") (pinfunction "1_1") (pintype "passive"))
      (node (ref "U$9") (pin "2") (pinfunction "2_2") (pintype "bidirectional"))
    )
    (net (code "49") (name "Net-(R14-Pad1)") (class "Default")
      (node (ref "R14") (pin "1") (pinfunction "1_1") (pintype "passive"))
      (node (ref "R22") (pin "1") (pinfunction "1_1") (pintype "passive"))
      (node (ref "U$10") (pin "2") (pinfunction "2_2") (pintype "bidirectional"))
    )
    (net (code "50") (name "Net-(R15-Pad1)") (class "Default")
      (node (ref "R15") (pin "1") (pinfunction "1_1") (pintype "passive"))
      (node (ref "R23") (pin "1") (pinfunction "1_1") (pintype "passive"))
      (node (ref "U$8") (pin "2") (pinfunction "2_2") (pintype "bidirectional"))
    )
    (net (code "51") (name "Net-(R16-Pad1)") (class "Default")
      (node (ref "R16") (pin "1") (pinfunction "1_1") (pintype "passive"))
      (node (ref "R24") (pin "1") (pinfunction "1_1") (pintype "passive"))
      (node (ref "U$7") (pin "2") (pinfunction "2_2") (pintype "bidirectional"))
    )
    (net (code "52") (name "Net-(R17-Pad1)") (class "Default")
      (node (ref "R17") (pin "1") (pinfunction "1_1") (pintype "passive"))
      (node (ref "R25") (pin "1") (pinfunction "1_1") (pintype "passive"))
      (node (ref "U$12") (pin "2") (pinfunction "2_2") (pintype "bidirectional"))
    )
    (net (code "53") (name "Net-(R18-Pad1)") (class "Default")
      (node (ref "R18") (pin "1") (pinfunction "1_1") (pintype "passive"))
      (node (ref "R26") (pin "1") (pinfunction "1_1") (pintype "passive"))
      (node (ref "U$11") (pin "2") (pinfunction "2_2") (pintype "bidirectional"))
    )
    (net (code "54") (name "Net-(R19-Pad1)") (class "Default")
      (node (ref "R19") (pin "1") (pinfunction "1_1") (pintype "passive"))
      (node (ref "R27") (pin "1") (pinfunction "1_1") (pintype "passive"))
      (node (ref "U$5") (pin "2") (pinfunction "2_2") (pintype "bidirectional"))
    )
    (net (code "55") (name "Net-(R20-Pad1)") (class "Default")
      (node (ref "R20") (pin "1") (pinfunction "1_1") (pintype "passive"))
      (node (ref "R28") (pin "1") (pinfunction "1_1") (pintype "passive"))
      (node (ref "U$6") (pin "2") (pinfunction "2_2") (pintype "bidirectional"))
    )
    (net (code "56") (name "Net-(R21-Pad2)") (class "Default")
      (node (ref "R21") (pin "2") (pinfunction "2_2") (pintype "passive"))
      (node (ref "R22") (pin "2") (pinfunction "2_2") (pintype "passive"))
      (node (ref "R23") (pin "2") (pinfunction "2_2") (pintype "passive"))
      (node (ref "R24") (pin "2") (pinfunction "2_2") (pintype "passive"))
      (node (ref "R7") (pin "1") (pinfunction "1_1") (pintype "passive"))
    )
    (net (code "57") (name "Net-(R25-Pad2)") (class "Default")
      (node (ref "R25") (pin "2") (pinfunction "2_2") (pintype "passive"))
      (node (ref "R26") (pin "2") (pinfunction "2_2") (pintype "passive"))
      (node (ref "R27") (pin "2") (pinfunction "2_2") (pintype "passive"))
      (node (ref "R28") (pin "2") (pinfunction "2_2") (pintype "passive"))
      (node (ref "R8") (pin "1") (pinfunction "1_1") (pintype "passive"))
    )
    (net (code "58") (name "Net-(R33-Pad1)") (class "Default")
      (node (ref "R33") (pin "1") (pinfunction "1_1") (pintype "passive"))
      (node (ref "R34") (pin "2") (pinfunction "2_2") (pintype "passive"))
      (node (ref "R5") (pin "1") (pinfunction "1_1") (pintype "passive"))
    )
    (net (code "59") (name "Net-(R37-Pad1)") (class "Default")
      (node (ref "R37") (pin "1") (pinfunction "1_1") (pintype "passive"))
      (node (ref "R38") (pin "2") (pinfunction "2_2") (pintype "passive"))
      (node (ref "R6") (pin "1") (pinfunction "1_1") (pintype "passive"))
    )
    (net (code "60") (name "Net-(R43-Pad2)") (class "Default")
      (node (ref "R43") (pin "2") (pinfunction "2_2") (pintype "passive"))
      (node (ref "U$1") (pin "2") (pinfunction "2_2") (pintype "bidirectional"))
    )
    (net (code "61") (name "Net-(R44-Pad2)") (class "Default")
      (node (ref "R44") (pin "2") (pinfunction "2_2") (pintype "passive"))
      (node (ref "U$2") (pin "2") (pinfunction "2_2") (pintype "bidirectional"))
    )
    (net (code "62") (name "unconnected-(J1-Pad4)") (class "Default")
      (node (ref "J1") (pin "4") (pinfunction "4_4") (pintype "passive"))
    )
    (net (code "63") (name "unconnected-(J1-Pad6)") (class "Default")
      (node (ref "J1") (pin "6") (pinfunction "6_6") (pintype "passive"))
    )
    (net (code "64") (name "unconnected-(J1-Pad11)") (class "Default")
      (node (ref "J1") (pin "11") (pinfunction "11_11") (pintype "passive"))
    )
    (net (code "65") (name "unconnected-(J1-Pad12)") (class "Default")
      (node (ref "J1") (pin "12") (pinfunction "12_12") (pintype "passive"))
    )
    (net (code "66") (name "unconnected-(J1-Pad13)") (class "Default")
      (node (ref "J1") (pin "13") (pinfunction "13_13") (pintype "passive"))
    )
    (net (code "67") (name "unconnected-(J1-Pad14)") (class "Default")
      (node (ref "J1") (pin "14") (pinfunction "14_14") (pintype "passive"))
    )
    (net (code "68") (name "unconnected-(J1-Pad15)") (class "Default")
      (node (ref "J1") (pin "15") (pinfunction "15_15") (pintype "passive"))
    )
    (net (code "69") (name "unconnected-(J1-Pad16)") (class "Default")
      (node (ref "J1") (pin "16") (pinfunction "16_16") (pintype "passive"))
    )
    (net (code "70") (name "unconnected-(X3B-S-Pad2)") (class "Default")
      (node (ref "X3") (pin "2") (pinfunction "S_2") (pintype "passive"))
    )
  )
)
